# nrfled.net
KiCad netlist of a schematic drawn in EAGLE
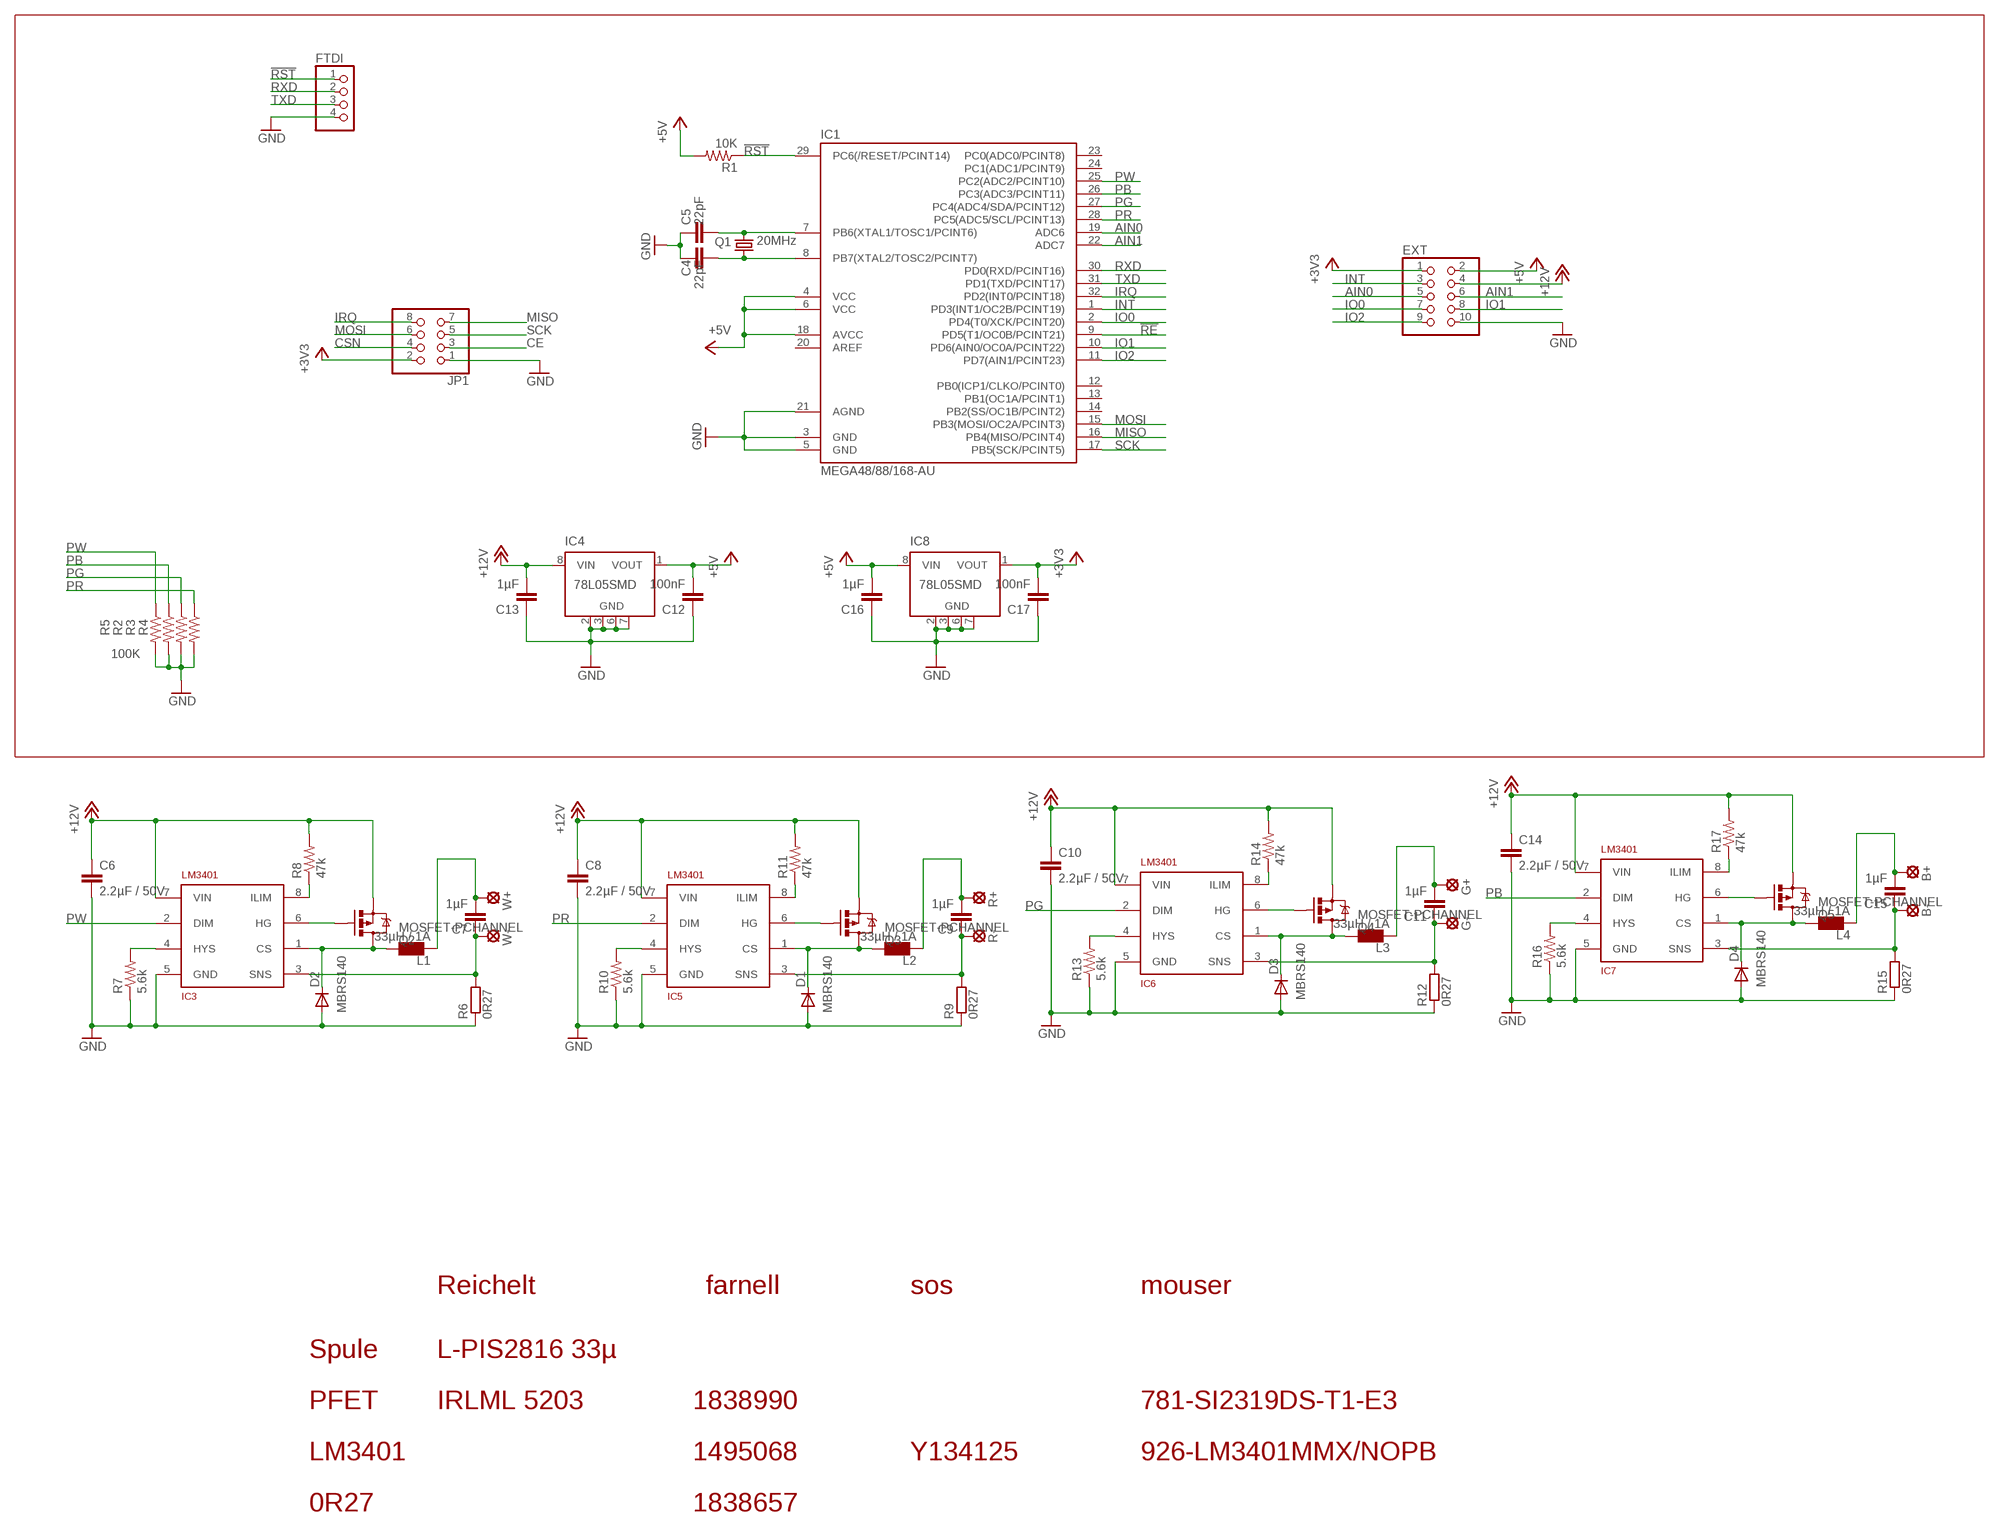
[diagram p0: schematic, sheet 1]

(export (version "E")
  (design (tool "Eeschema 10.0.6"))
  (components
    (comp (ref "B+")
      (value "SE14")
      (footprint "eagle-import:SE14")
      (libsource (lib "eagle-import") (part "SE14"))
    )
    (comp (ref "B-")
      (value "SE14")
      (footprint "eagle-import:SE14")
      (libsource (lib "eagle-import") (part "SE14"))
    )
    (comp (ref "C4")
      (value "22pF")
      (footprint "eagle-import:0402-CAP")
      (libsource (lib "eagle-import") (part "CAP0402-CAP"))
    )
    (comp (ref "C5")
      (value "22pF")
      (footprint "eagle-import:0402-CAP")
      (libsource (lib "eagle-import") (part "CAP0402-CAP"))
    )
    (comp (ref "C6")
      (value "2.2µF / 50V")
      (footprint "eagle-import:C1210")
      (libsource (lib "eagle-import") (part "C-EUC1210"))
    )
    (comp (ref "C7")
      (value "1µF")
      (footprint "eagle-import:0805")
      (libsource (lib "eagle-import") (part "CAP0805"))
    )
    (comp (ref "C8")
      (value "2.2µF / 50V")
      (footprint "eagle-import:C1210")
      (libsource (lib "eagle-import") (part "C-EUC1210"))
    )
    (comp (ref "C9")
      (value "1µF")
      (footprint "eagle-import:0805")
      (libsource (lib "eagle-import") (part "CAP0805"))
    )
    (comp (ref "C10")
      (value "2.2µF / 50V")
      (footprint "eagle-import:C1210")
      (libsource (lib "eagle-import") (part "C-EUC1210"))
    )
    (comp (ref "C11")
      (value "1µF")
      (footprint "eagle-import:0805")
      (libsource (lib "eagle-import") (part "CAP0805"))
    )
    (comp (ref "C12")
      (value "100nF")
      (footprint "eagle-import:0402-CAP")
      (libsource (lib "eagle-import") (part "CAP0402-CAP"))
    )
    (comp (ref "C13")
      (value "1µF")
      (footprint "eagle-import:0805")
      (libsource (lib "eagle-import") (part "CAP0805"))
    )
    (comp (ref "C14")
      (value "2.2µF / 50V")
      (footprint "eagle-import:C1210")
      (libsource (lib "eagle-import") (part "C-EUC1210"))
    )
    (comp (ref "C15")
      (value "1µF")
      (footprint "eagle-import:0805")
      (libsource (lib "eagle-import") (part "CAP0805"))
    )
    (comp (ref "C16")
      (value "1µF")
      (footprint "eagle-import:0805")
      (libsource (lib "eagle-import") (part "CAP0805"))
    )
    (comp (ref "C17")
      (value "100nF")
      (footprint "eagle-import:0402-CAP")
      (libsource (lib "eagle-import") (part "CAP0402-CAP"))
    )
    (comp (ref "D1")
      (value "MBRS140")
      (footprint "eagle-import:SMB")
      (libsource (lib "eagle-import") (part "DIODE-SMB"))
    )
    (comp (ref "D2")
      (value "MBRS140")
      (footprint "eagle-import:SMB")
      (libsource (lib "eagle-import") (part "DIODE-SMB"))
    )
    (comp (ref "D3")
      (value "MBRS140")
      (footprint "eagle-import:SMB")
      (libsource (lib "eagle-import") (part "DIODE-SMB"))
    )
    (comp (ref "D4")
      (value "MBRS140")
      (footprint "eagle-import:SMB")
      (libsource (lib "eagle-import") (part "DIODE-SMB"))
    )
    (comp (ref "EXT")
      (value "PINHD-2X5")
      (footprint "eagle-import:2X05")
      (libsource (lib "eagle-import") (part "PINHD-2X5"))
    )
    (comp (ref "FTDI")
      (value "PINHD-1X4")
      (footprint "eagle-import:1X04")
      (libsource (lib "eagle-import") (part "PINHD-1X4"))
    )
    (comp (ref "G+")
      (value "SE14")
      (footprint "eagle-import:SE14")
      (libsource (lib "eagle-import") (part "SE14"))
    )
    (comp (ref "G-")
      (value "SE14")
      (footprint "eagle-import:SE14")
      (libsource (lib "eagle-import") (part "SE14"))
    )
    (comp (ref "IC1")
      (value "MEGA48/88/168-AU")
      (footprint "eagle-import:TQFP32-08")
      (libsource (lib "eagle-import") (part "MEGA48/88/168-AU"))
    )
    (comp (ref "IC3")
      (value "LM3401")
      (footprint "eagle-import:MSOP8")
      (libsource (lib "eagle-import") (part "LM3401"))
    )
    (comp (ref "IC4")
      (value "78L05SMD")
      (footprint "eagle-import:SO08")
      (libsource (lib "eagle-import") (part "78LSMD05"))
    )
    (comp (ref "IC5")
      (value "LM3401")
      (footprint "eagle-import:MSOP8")
      (libsource (lib "eagle-import") (part "LM3401"))
    )
    (comp (ref "IC6")
      (value "LM3401")
      (footprint "eagle-import:MSOP8")
      (libsource (lib "eagle-import") (part "LM3401"))
    )
    (comp (ref "IC7")
      (value "LM3401")
      (footprint "eagle-import:MSOP8")
      (libsource (lib "eagle-import") (part "LM3401"))
    )
    (comp (ref "IC8")
      (value "78L05SMD")
      (footprint "eagle-import:SO08")
      (libsource (lib "eagle-import") (part "78LSMD05"))
    )
    (comp (ref "JP1")
      (value "PINHD-2X4")
      (footprint "eagle-import:2X04")
      (libsource (lib "eagle-import") (part "PINHD-2X4"))
    )
    (comp (ref "L1")
      (value "33µH / 1A")
      (footprint "eagle-import:PIS2816")
      (libsource (lib "eagle-import") (part "L_PIS2816"))
    )
    (comp (ref "L2")
      (value "33µH / 1A")
      (footprint "eagle-import:PIS2816")
      (libsource (lib "eagle-import") (part "L_PIS2816"))
    )
    (comp (ref "L3")
      (value "33µH / 1A")
      (footprint "eagle-import:PIS2816")
      (libsource (lib "eagle-import") (part "L_PIS2816"))
    )
    (comp (ref "L4")
      (value "33µH / 1A")
      (footprint "eagle-import:PIS2816")
      (libsource (lib "eagle-import") (part "L_PIS2816"))
    )
    (comp (ref "Q1")
      (value "20MHz")
      (footprint "eagle-import:X22")
      (libsource (lib "eagle-import") (part "X22-OSCILLATOR"))
    )
    (comp (ref "Q2")
      (value "MOSFET-PCHANNEL")
      (footprint "eagle-import:SOT23")
      (libsource (lib "eagle-import") (part "MOSFET-PCHANNEL"))
    )
    (comp (ref "Q3")
      (value "MOSFET-PCHANNEL")
      (footprint "eagle-import:SOT23")
      (libsource (lib "eagle-import") (part "MOSFET-PCHANNEL"))
    )
    (comp (ref "Q4")
      (value "MOSFET-PCHANNEL")
      (footprint "eagle-import:SOT23")
      (libsource (lib "eagle-import") (part "MOSFET-PCHANNEL"))
    )
    (comp (ref "Q5")
      (value "MOSFET-PCHANNEL")
      (footprint "eagle-import:SOT23")
      (libsource (lib "eagle-import") (part "MOSFET-PCHANNEL"))
    )
    (comp (ref "R+")
      (value "SE14")
      (footprint "eagle-import:SE14")
      (libsource (lib "eagle-import") (part "SE14"))
    )
    (comp (ref "R-")
      (value "SE14")
      (footprint "eagle-import:SE14")
      (libsource (lib "eagle-import") (part "SE14"))
    )
    (comp (ref "R1")
      (value "10K")
      (footprint "eagle-import:0402-RES")
      (libsource (lib "eagle-import") (part "RESISTOR0402-RES"))
    )
    (comp (ref "R2")
      (value "100K")
      (footprint "eagle-import:0402-RES")
      (libsource (lib "eagle-import") (part "RESISTOR0402-RES"))
    )
    (comp (ref "R3")
      (value "100K")
      (footprint "eagle-import:0402-RES")
      (libsource (lib "eagle-import") (part "RESISTOR0402-RES"))
    )
    (comp (ref "R4")
      (value "100K")
      (footprint "eagle-import:0402-RES")
      (libsource (lib "eagle-import") (part "RESISTOR0402-RES"))
    )
    (comp (ref "R5")
      (value "100K")
      (footprint "eagle-import:0402-RES")
      (libsource (lib "eagle-import") (part "RESISTOR0402-RES"))
    )
    (comp (ref "R6")
      (value "0R27")
      (footprint "eagle-import:R1206")
      (libsource (lib "eagle-import") (part "R-EU_R1206"))
    )
    (comp (ref "R7")
      (value "5.6k")
      (footprint "eagle-import:0805")
      (libsource (lib "eagle-import") (part "RESISTOR0805-RES"))
    )
    (comp (ref "R8")
      (value "47k")
      (footprint "eagle-import:0805")
      (libsource (lib "eagle-import") (part "RESISTOR0805-RES"))
    )
    (comp (ref "R9")
      (value "0R27")
      (footprint "eagle-import:R1206")
      (libsource (lib "eagle-import") (part "R-EU_R1206"))
    )
    (comp (ref "R10")
      (value "5.6k")
      (footprint "eagle-import:0805")
      (libsource (lib "eagle-import") (part "RESISTOR0805-RES"))
    )
    (comp (ref "R11")
      (value "47k")
      (footprint "eagle-import:0805")
      (libsource (lib "eagle-import") (part "RESISTOR0805-RES"))
    )
    (comp (ref "R12")
      (value "0R27")
      (footprint "eagle-import:R1206")
      (libsource (lib "eagle-import") (part "R-EU_R1206"))
    )
    (comp (ref "R13")
      (value "5.6k")
      (footprint "eagle-import:0805")
      (libsource (lib "eagle-import") (part "RESISTOR0805-RES"))
    )
    (comp (ref "R14")
      (value "47k")
      (footprint "eagle-import:0805")
      (libsource (lib "eagle-import") (part "RESISTOR0805-RES"))
    )
    (comp (ref "R15")
      (value "0R27")
      (footprint "eagle-import:R1206")
      (libsource (lib "eagle-import") (part "R-EU_R1206"))
    )
    (comp (ref "R16")
      (value "5.6k")
      (footprint "eagle-import:0805")
      (libsource (lib "eagle-import") (part "RESISTOR0805-RES"))
    )
    (comp (ref "R17")
      (value "47k")
      (footprint "eagle-import:0805")
      (libsource (lib "eagle-import") (part "RESISTOR0805-RES"))
    )
    (comp (ref "W+")
      (value "SE14")
      (footprint "eagle-import:SE14")
      (libsource (lib "eagle-import") (part "SE14"))
    )
    (comp (ref "W-")
      (value "SE14")
      (footprint "eagle-import:SE14")
      (libsource (lib "eagle-import") (part "SE14"))
    )
  )
  (nets
    (net (code "1") (name "+3V3") (class "Default")
      (node (ref "C17") (pin "2") (pinfunction "2_2") (pintype "passive"))
      (node (ref "EXT") (pin "1") (pinfunction "1_1") (pintype "passive"))
      (node (ref "IC8") (pin "1") (pinfunction "VOUT_1") (pintype "output"))
      (node (ref "JP1") (pin "2") (pinfunction "2_2") (pintype "passive"))
    )
    (net (code "2") (name "+5V") (class "Default")
      (node (ref "C12") (pin "2") (pinfunction "2_2") (pintype "passive"))
      (node (ref "C16") (pin "2") (pinfunction "2_2") (pintype "passive"))
      (node (ref "EXT") (pin "2") (pinfunction "2_2") (pintype "passive"))
      (node (ref "IC1") (pin "18") (pinfunction "AVCC_18") (pintype "passive"))
      (node (ref "IC1") (pin "4") (pinfunction "VCC_4") (pintype "power_in"))
      (node (ref "IC1") (pin "6") (pinfunction "VCC_6") (pintype "power_in"))
      (node (ref "IC4") (pin "1") (pinfunction "VOUT_1") (pintype "output"))
      (node (ref "IC8") (pin "8") (pinfunction "VIN_8") (pintype "passive"))
      (node (ref "R1") (pin "2") (pinfunction "2_2") (pintype "passive"))
    )
    (net (code "3") (name "+12V") (class "Default")
      (node (ref "C10") (pin "1") (pinfunction "1_1") (pintype "passive"))
      (node (ref "C13") (pin "2") (pinfunction "2_2") (pintype "passive"))
      (node (ref "C14") (pin "1") (pinfunction "1_1") (pintype "passive"))
      (node (ref "C6") (pin "1") (pinfunction "1_1") (pintype "passive"))
      (node (ref "C8") (pin "1") (pinfunction "1_1") (pintype "passive"))
      (node (ref "EXT") (pin "4") (pinfunction "4_4") (pintype "passive"))
      (node (ref "IC3") (pin "7") (pinfunction "VIN_7") (pintype "bidirectional"))
      (node (ref "IC4") (pin "8") (pinfunction "VIN_8") (pintype "passive"))
      (node (ref "IC5") (pin "7") (pinfunction "VIN_7") (pintype "bidirectional"))
      (node (ref "IC6") (pin "7") (pinfunction "VIN_7") (pintype "bidirectional"))
      (node (ref "IC7") (pin "7") (pinfunction "VIN_7") (pintype "bidirectional"))
      (node (ref "Q2") (pin "2") (pinfunction "S_2") (pintype "passive"))
      (node (ref "Q3") (pin "2") (pinfunction "S_2") (pintype "passive"))
      (node (ref "Q4") (pin "2") (pinfunction "S_2") (pintype "passive"))
      (node (ref "Q5") (pin "2") (pinfunction "S_2") (pintype "passive"))
      (node (ref "R11") (pin "2") (pinfunction "2_2") (pintype "passive"))
      (node (ref "R14") (pin "2") (pinfunction "2_2") (pintype "passive"))
      (node (ref "R17") (pin "2") (pinfunction "2_2") (pintype "passive"))
      (node (ref "R8") (pin "2") (pinfunction "2_2") (pintype "passive"))
    )
    (net (code "4") (name "/AIN0") (class "Default")
      (node (ref "EXT") (pin "5") (pinfunction "5_5") (pintype "passive"))
      (node (ref "IC1") (pin "19") (pinfunction "ADC6_19") (pintype "passive"))
    )
    (net (code "5") (name "/AIN1") (class "Default")
      (node (ref "EXT") (pin "6") (pinfunction "6_6") (pintype "passive"))
      (node (ref "IC1") (pin "22") (pinfunction "ADC7_22") (pintype "passive"))
    )
    (net (code "6") (name "/CE") (class "Default")
      (node (ref "JP1") (pin "3") (pinfunction "3_3") (pintype "passive"))
    )
    (net (code "7") (name "/CSN") (class "Default")
      (node (ref "JP1") (pin "4") (pinfunction "4_4") (pintype "passive"))
    )
    (net (code "8") (name "/INT") (class "Default")
      (node (ref "EXT") (pin "3") (pinfunction "3_3") (pintype "passive"))
      (node (ref "IC1") (pin "1") (pinfunction "PD3(INT1/OC2B/PCINT19)_1") (pintype "bidirectional"))
    )
    (net (code "9") (name "/IO0") (class "Default")
      (node (ref "EXT") (pin "7") (pinfunction "7_7") (pintype "passive"))
      (node (ref "IC1") (pin "2") (pinfunction "PD4(T0/XCK/PCINT20)_2") (pintype "bidirectional"))
    )
    (net (code "10") (name "/IO1") (class "Default")
      (node (ref "EXT") (pin "8") (pinfunction "8_8") (pintype "passive"))
      (node (ref "IC1") (pin "10") (pinfunction "PD6(AIN0/OC0A/PCINT22)_10") (pintype "bidirectional"))
    )
    (net (code "11") (name "/IO2") (class "Default")
      (node (ref "EXT") (pin "9") (pinfunction "9_9") (pintype "passive"))
      (node (ref "IC1") (pin "11") (pinfunction "PD7(AIN1/PCINT23)_11") (pintype "bidirectional"))
    )
    (net (code "12") (name "/IRQ") (class "Default")
      (node (ref "IC1") (pin "32") (pinfunction "PD2(INT0/PCINT18)_32") (pintype "bidirectional"))
      (node (ref "JP1") (pin "8") (pinfunction "8_8") (pintype "passive"))
    )
    (net (code "13") (name "/MISO") (class "Default")
      (node (ref "IC1") (pin "16") (pinfunction "PB4(MISO/PCINT4)_16") (pintype "bidirectional"))
      (node (ref "JP1") (pin "7") (pinfunction "7_7") (pintype "passive"))
    )
    (net (code "14") (name "/MOSI") (class "Default")
      (node (ref "IC1") (pin "15") (pinfunction "PB3(MOSI/OC2A/PCINT3)_15") (pintype "bidirectional"))
      (node (ref "JP1") (pin "6") (pinfunction "6_6") (pintype "passive"))
    )
    (net (code "15") (name "/PB") (class "Default")
      (node (ref "IC1") (pin "26") (pinfunction "PC3(ADC3/PCINT11)_26") (pintype "bidirectional"))
      (node (ref "IC7") (pin "2") (pinfunction "DIM_2") (pintype "bidirectional"))
      (node (ref "R2") (pin "1") (pinfunction "1_1") (pintype "passive"))
    )
    (net (code "16") (name "/PG") (class "Default")
      (node (ref "IC1") (pin "27") (pinfunction "PC4(ADC4/SDA/PCINT12)_27") (pintype "bidirectional"))
      (node (ref "IC6") (pin "2") (pinfunction "DIM_2") (pintype "bidirectional"))
      (node (ref "R3") (pin "1") (pinfunction "1_1") (pintype "passive"))
    )
    (net (code "17") (name "/PR") (class "Default")
      (node (ref "IC1") (pin "28") (pinfunction "PC5(ADC5/SCL/PCINT13)_28") (pintype "bidirectional"))
      (node (ref "IC5") (pin "2") (pinfunction "DIM_2") (pintype "bidirectional"))
      (node (ref "R4") (pin "1") (pinfunction "1_1") (pintype "passive"))
    )
    (net (code "18") (name "/PW") (class "Default")
      (node (ref "IC1") (pin "25") (pinfunction "PC2(ADC2/PCINT10)_25") (pintype "bidirectional"))
      (node (ref "IC3") (pin "2") (pinfunction "DIM_2") (pintype "bidirectional"))
      (node (ref "R5") (pin "1") (pinfunction "1_1") (pintype "passive"))
    )
    (net (code "19") (name "/RXD") (class "Default")
      (node (ref "FTDI") (pin "2") (pinfunction "2_2") (pintype "passive"))
      (node (ref "IC1") (pin "30") (pinfunction "PD0(RXD/PCINT16)_30") (pintype "bidirectional"))
    )
    (net (code "20") (name "/SCK") (class "Default")
      (node (ref "IC1") (pin "17") (pinfunction "PB5(SCK/PCINT5)_17") (pintype "bidirectional"))
      (node (ref "JP1") (pin "5") (pinfunction "5_5") (pintype "passive"))
    )
    (net (code "21") (name "/TXD") (class "Default")
      (node (ref "FTDI") (pin "3") (pinfunction "3_3") (pintype "passive"))
      (node (ref "IC1") (pin "31") (pinfunction "PD1(TXD/PCINT17)_31") (pintype "bidirectional"))
    )
    (net (code "22") (name "/~{RE}") (class "Default")
      (node (ref "IC1") (pin "9") (pinfunction "PD5(T1/OC0B/PCINT21)_9") (pintype "bidirectional"))
    )
    (net (code "23") (name "/~{RST}") (class "Default")
      (node (ref "FTDI") (pin "1") (pinfunction "1_1") (pintype "passive"))
      (node (ref "IC1") (pin "29") (pinfunction "PC6(/RESET/PCINT14)_29") (pintype "bidirectional"))
      (node (ref "R1") (pin "1") (pinfunction "1_1") (pintype "passive"))
    )
    (net (code "24") (name "GND") (class "Default")
      (node (ref "C10") (pin "2") (pinfunction "2_2") (pintype "passive"))
      (node (ref "C12") (pin "1") (pinfunction "1_1") (pintype "passive"))
      (node (ref "C13") (pin "1") (pinfunction "1_1") (pintype "passive"))
      (node (ref "C14") (pin "2") (pinfunction "2_2") (pintype "passive"))
      (node (ref "C16") (pin "1") (pinfunction "1_1") (pintype "passive"))
      (node (ref "C17") (pin "1") (pinfunction "1_1") (pintype "passive"))
      (node (ref "C4") (pin "1") (pinfunction "1_1") (pintype "passive"))
      (node (ref "C5") (pin "1") (pinfunction "1_1") (pintype "passive"))
      (node (ref "C6") (pin "2") (pinfunction "2_2") (pintype "passive"))
      (node (ref "C8") (pin "2") (pinfunction "2_2") (pintype "passive"))
      (node (ref "D1") (pin "A") (pinfunction "A_A") (pintype "passive"))
      (node (ref "D2") (pin "A") (pinfunction "A_A") (pintype "passive"))
      (node (ref "D3") (pin "A") (pinfunction "A_A") (pintype "passive"))
      (node (ref "D4") (pin "A") (pinfunction "A_A") (pintype "passive"))
      (node (ref "EXT") (pin "10") (pinfunction "10_10") (pintype "passive"))
      (node (ref "FTDI") (pin "4") (pinfunction "4_4") (pintype "passive"))
      (node (ref "IC1") (pin "21") (pinfunction "AGND_21") (pintype "power_in"))
      (node (ref "IC1") (pin "3") (pinfunction "GND_3") (pintype "power_in"))
      (node (ref "IC1") (pin "5") (pinfunction "GND_5") (pintype "power_in"))
      (node (ref "IC3") (pin "5") (pinfunction "GND_5") (pintype "bidirectional"))
      (node (ref "IC4") (pin "2") (pinfunction "GND_2") (pintype "power_in"))
      (node (ref "IC4") (pin "3") (pinfunction "GND_3") (pintype "power_in"))
      (node (ref "IC4") (pin "6") (pinfunction "GND_6") (pintype "power_in"))
      (node (ref "IC4") (pin "7") (pinfunction "GND_7") (pintype "power_in"))
      (node (ref "IC5") (pin "5") (pinfunction "GND_5") (pintype "bidirectional"))
      (node (ref "IC6") (pin "5") (pinfunction "GND_5") (pintype "bidirectional"))
      (node (ref "IC7") (pin "5") (pinfunction "GND_5") (pintype "bidirectional"))
      (node (ref "IC8") (pin "2") (pinfunction "GND_2") (pintype "power_in"))
      (node (ref "IC8") (pin "3") (pinfunction "GND_3") (pintype "power_in"))
      (node (ref "IC8") (pin "6") (pinfunction "GND_6") (pintype "power_in"))
      (node (ref "IC8") (pin "7") (pinfunction "GND_7") (pintype "power_in"))
      (node (ref "JP1") (pin "1") (pinfunction "1_1") (pintype "passive"))
      (node (ref "R10") (pin "1") (pinfunction "1_1") (pintype "passive"))
      (node (ref "R12") (pin "1") (pinfunction "1_1") (pintype "passive"))
      (node (ref "R13") (pin "1") (pinfunction "1_1") (pintype "passive"))
      (node (ref "R15") (pin "1") (pinfunction "1_1") (pintype "passive"))
      (node (ref "R16") (pin "1") (pinfunction "1_1") (pintype "passive"))
      (node (ref "R2") (pin "2") (pinfunction "2_2") (pintype "passive"))
      (node (ref "R3") (pin "2") (pinfunction "2_2") (pintype "passive"))
      (node (ref "R4") (pin "2") (pinfunction "2_2") (pintype "passive"))
      (node (ref "R5") (pin "2") (pinfunction "2_2") (pintype "passive"))
      (node (ref "R6") (pin "1") (pinfunction "1_1") (pintype "passive"))
      (node (ref "R7") (pin "1") (pinfunction "1_1") (pintype "passive"))
      (node (ref "R9") (pin "1") (pinfunction "1_1") (pintype "passive"))
    )
    (net (code "25") (name "Net-(IC1-PB6(XTAL1{slash}TOSC1{slash}PCINT6))") (class "Default")
      (node (ref "C5") (pin "2") (pinfunction "2_2") (pintype "passive"))
      (node (ref "IC1") (pin "7") (pinfunction "PB6(XTAL1/TOSC1/PCINT6)_7") (pintype "bidirectional"))
      (node (ref "Q1") (pin "3") (pinfunction "2_3") (pintype "passive"))
    )
    (net (code "26") (name "Net-(IC1-PB7(XTAL2{slash}TOSC2{slash}PCINT7))") (class "Default")
      (node (ref "C4") (pin "2") (pinfunction "2_2") (pintype "passive"))
      (node (ref "IC1") (pin "8") (pinfunction "PB7(XTAL2/TOSC2/PCINT7)_8") (pintype "bidirectional"))
      (node (ref "Q1") (pin "1") (pinfunction "1_1") (pintype "passive"))
    )
    (net (code "27") (name "Net-(IC3-CS)") (class "Default")
      (node (ref "D2") (pin "C") (pinfunction "C_C") (pintype "passive"))
      (node (ref "IC3") (pin "1") (pinfunction "CS_1") (pintype "bidirectional"))
      (node (ref "L1") (pin "P$1") (pinfunction "1_P$1") (pintype "passive"))
      (node (ref "Q2") (pin "3") (pinfunction "D_3") (pintype "passive"))
    )
    (net (code "28") (name "Net-(IC3-HG)") (class "Default")
      (node (ref "IC3") (pin "6") (pinfunction "HG_6") (pintype "bidirectional"))
      (node (ref "Q2") (pin "1") (pinfunction "G_1") (pintype "passive"))
    )
    (net (code "29") (name "Net-(IC3-HYS)") (class "Default")
      (node (ref "IC3") (pin "4") (pinfunction "HYS_4") (pintype "bidirectional"))
      (node (ref "R7") (pin "2") (pinfunction "2_2") (pintype "passive"))
    )
    (net (code "30") (name "Net-(IC3-ILIM)") (class "Default")
      (node (ref "IC3") (pin "8") (pinfunction "ILIM_8") (pintype "bidirectional"))
      (node (ref "R8") (pin "1") (pinfunction "1_1") (pintype "passive"))
    )
    (net (code "31") (name "Net-(IC3-SNS)") (class "Default")
      (node (ref "C7") (pin "1") (pinfunction "1_1") (pintype "passive"))
      (node (ref "IC3") (pin "3") (pinfunction "SNS_3") (pintype "bidirectional"))
      (node (ref "R6") (pin "2") (pinfunction "2_2") (pintype "passive"))
      (node (ref "W-") (pin "MP") (pinfunction "MP_MP") (pintype "passive"))
    )
    (net (code "32") (name "Net-(IC5-CS)") (class "Default")
      (node (ref "D1") (pin "C") (pinfunction "C_C") (pintype "passive"))
      (node (ref "IC5") (pin "1") (pinfunction "CS_1") (pintype "bidirectional"))
      (node (ref "L2") (pin "P$1") (pinfunction "1_P$1") (pintype "passive"))
      (node (ref "Q3") (pin "3") (pinfunction "D_3") (pintype "passive"))
    )
    (net (code "33") (name "Net-(IC5-HG)") (class "Default")
      (node (ref "IC5") (pin "6") (pinfunction "HG_6") (pintype "bidirectional"))
      (node (ref "Q3") (pin "1") (pinfunction "G_1") (pintype "passive"))
    )
    (net (code "34") (name "Net-(IC5-HYS)") (class "Default")
      (node (ref "IC5") (pin "4") (pinfunction "HYS_4") (pintype "bidirectional"))
      (node (ref "R10") (pin "2") (pinfunction "2_2") (pintype "passive"))
    )
    (net (code "35") (name "Net-(IC5-ILIM)") (class "Default")
      (node (ref "IC5") (pin "8") (pinfunction "ILIM_8") (pintype "bidirectional"))
      (node (ref "R11") (pin "1") (pinfunction "1_1") (pintype "passive"))
    )
    (net (code "36") (name "Net-(IC5-SNS)") (class "Default")
      (node (ref "C9") (pin "1") (pinfunction "1_1") (pintype "passive"))
      (node (ref "IC5") (pin "3") (pinfunction "SNS_3") (pintype "bidirectional"))
      (node (ref "R-") (pin "MP") (pinfunction "MP_MP") (pintype "passive"))
      (node (ref "R9") (pin "2") (pinfunction "2_2") (pintype "passive"))
    )
    (net (code "37") (name "Net-(IC6-CS)") (class "Default")
      (node (ref "D3") (pin "C") (pinfunction "C_C") (pintype "passive"))
      (node (ref "IC6") (pin "1") (pinfunction "CS_1") (pintype "bidirectional"))
      (node (ref "L3") (pin "P$1") (pinfunction "1_P$1") (pintype "passive"))
      (node (ref "Q4") (pin "3") (pinfunction "D_3") (pintype "passive"))
    )
    (net (code "38") (name "Net-(IC6-HG)") (class "Default")
      (node (ref "IC6") (pin "6") (pinfunction "HG_6") (pintype "bidirectional"))
      (node (ref "Q4") (pin "1") (pinfunction "G_1") (pintype "passive"))
    )
    (net (code "39") (name "Net-(IC6-HYS)") (class "Default")
      (node (ref "IC6") (pin "4") (pinfunction "HYS_4") (pintype "bidirectional"))
      (node (ref "R13") (pin "2") (pinfunction "2_2") (pintype "passive"))
    )
    (net (code "40") (name "Net-(IC6-ILIM)") (class "Default")
      (node (ref "IC6") (pin "8") (pinfunction "ILIM_8") (pintype "bidirectional"))
      (node (ref "R14") (pin "1") (pinfunction "1_1") (pintype "passive"))
    )
    (net (code "41") (name "Net-(IC6-SNS)") (class "Default")
      (node (ref "C11") (pin "1") (pinfunction "1_1") (pintype "passive"))
      (node (ref "G-") (pin "MP") (pinfunction "MP_MP") (pintype "passive"))
      (node (ref "IC6") (pin "3") (pinfunction "SNS_3") (pintype "bidirectional"))
      (node (ref "R12") (pin "2") (pinfunction "2_2") (pintype "passive"))
    )
    (net (code "42") (name "Net-(IC7-CS)") (class "Default")
      (node (ref "D4") (pin "C") (pinfunction "C_C") (pintype "passive"))
      (node (ref "IC7") (pin "1") (pinfunction "CS_1") (pintype "bidirectional"))
      (node (ref "L4") (pin "P$1") (pinfunction "1_P$1") (pintype "passive"))
      (node (ref "Q5") (pin "3") (pinfunction "D_3") (pintype "passive"))
    )
    (net (code "43") (name "Net-(IC7-HG)") (class "Default")
      (node (ref "IC7") (pin "6") (pinfunction "HG_6") (pintype "bidirectional"))
      (node (ref "Q5") (pin "1") (pinfunction "G_1") (pintype "passive"))
    )
    (net (code "44") (name "Net-(IC7-HYS)") (class "Default")
      (node (ref "IC7") (pin "4") (pinfunction "HYS_4") (pintype "bidirectional"))
      (node (ref "R16") (pin "2") (pinfunction "2_2") (pintype "passive"))
    )
    (net (code "45") (name "Net-(IC7-ILIM)") (class "Default")
      (node (ref "IC7") (pin "8") (pinfunction "ILIM_8") (pintype "bidirectional"))
      (node (ref "R17") (pin "1") (pinfunction "1_1") (pintype "passive"))
    )
    (net (code "46") (name "Net-(IC7-SNS)") (class "Default")
      (node (ref "B-") (pin "MP") (pinfunction "MP_MP") (pintype "passive"))
      (node (ref "C15") (pin "1") (pinfunction "1_1") (pintype "passive"))
      (node (ref "IC7") (pin "3") (pinfunction "SNS_3") (pintype "bidirectional"))
      (node (ref "R15") (pin "2") (pinfunction "2_2") (pintype "passive"))
    )
    (net (code "47") (name "Net-(L1-2)") (class "Default")
      (node (ref "C7") (pin "2") (pinfunction "2_2") (pintype "passive"))
      (node (ref "L1") (pin "P$2") (pinfunction "2_P$2") (pintype "passive"))
      (node (ref "W+") (pin "MP") (pinfunction "MP_MP") (pintype "passive"))
    )
    (net (code "48") (name "Net-(L2-2)") (class "Default")
      (node (ref "C9") (pin "2") (pinfunction "2_2") (pintype "passive"))
      (node (ref "L2") (pin "P$2") (pinfunction "2_P$2") (pintype "passive"))
      (node (ref "R+") (pin "MP") (pinfunction "MP_MP") (pintype "passive"))
    )
    (net (code "49") (name "Net-(L3-2)") (class "Default")
      (node (ref "C11") (pin "2") (pinfunction "2_2") (pintype "passive"))
      (node (ref "G+") (pin "MP") (pinfunction "MP_MP") (pintype "passive"))
      (node (ref "L3") (pin "P$2") (pinfunction "2_P$2") (pintype "passive"))
    )
    (net (code "50") (name "Net-(L4-2)") (class "Default")
      (node (ref "B+") (pin "MP") (pinfunction "MP_MP") (pintype "passive"))
      (node (ref "C15") (pin "2") (pinfunction "2_2") (pintype "passive"))
      (node (ref "L4") (pin "P$2") (pinfunction "2_P$2") (pintype "passive"))
    )
    (net (code "51") (name "unconnected-(IC1-AREF-Pad20)") (class "Default")
      (node (ref "IC1") (pin "20") (pinfunction "AREF_20") (pintype "passive"))
    )
    (net (code "52") (name "unconnected-(IC1-PB0(ICP1{slash}CLKO{slash}PCINT0)-Pad12)") (class "Default")
      (node (ref "IC1") (pin "12") (pinfunction "PB0(ICP1/CLKO/PCINT0)_12") (pintype "bidirectional"))
    )
    (net (code "53") (name "unconnected-(IC1-PB1(OC1A{slash}PCINT1)-Pad13)") (class "Default")
      (node (ref "IC1") (pin "13") (pinfunction "PB1(OC1A/PCINT1)_13") (pintype "bidirectional"))
    )
    (net (code "54") (name "unconnected-(IC1-PB2(SS{slash}OC1B{slash}PCINT2)-Pad14)") (class "Default")
      (node (ref "IC1") (pin "14") (pinfunction "PB2(SS/OC1B/PCINT2)_14") (pintype "bidirectional"))
    )
    (net (code "55") (name "unconnected-(IC1-PC0(ADC0{slash}PCINT8)-Pad23)") (class "Default")
      (node (ref "IC1") (pin "23") (pinfunction "PC0(ADC0/PCINT8)_23") (pintype "bidirectional"))
    )
    (net (code "56") (name "unconnected-(IC1-PC1(ADC1{slash}PCINT9)-Pad24)") (class "Default")
      (node (ref "IC1") (pin "24") (pinfunction "PC1(ADC1/PCINT9)_24") (pintype "bidirectional"))
    )
  )
)
